# SIM5320_3G_Breakout.net
KiCad netlist of a schematic drawn in EAGLE
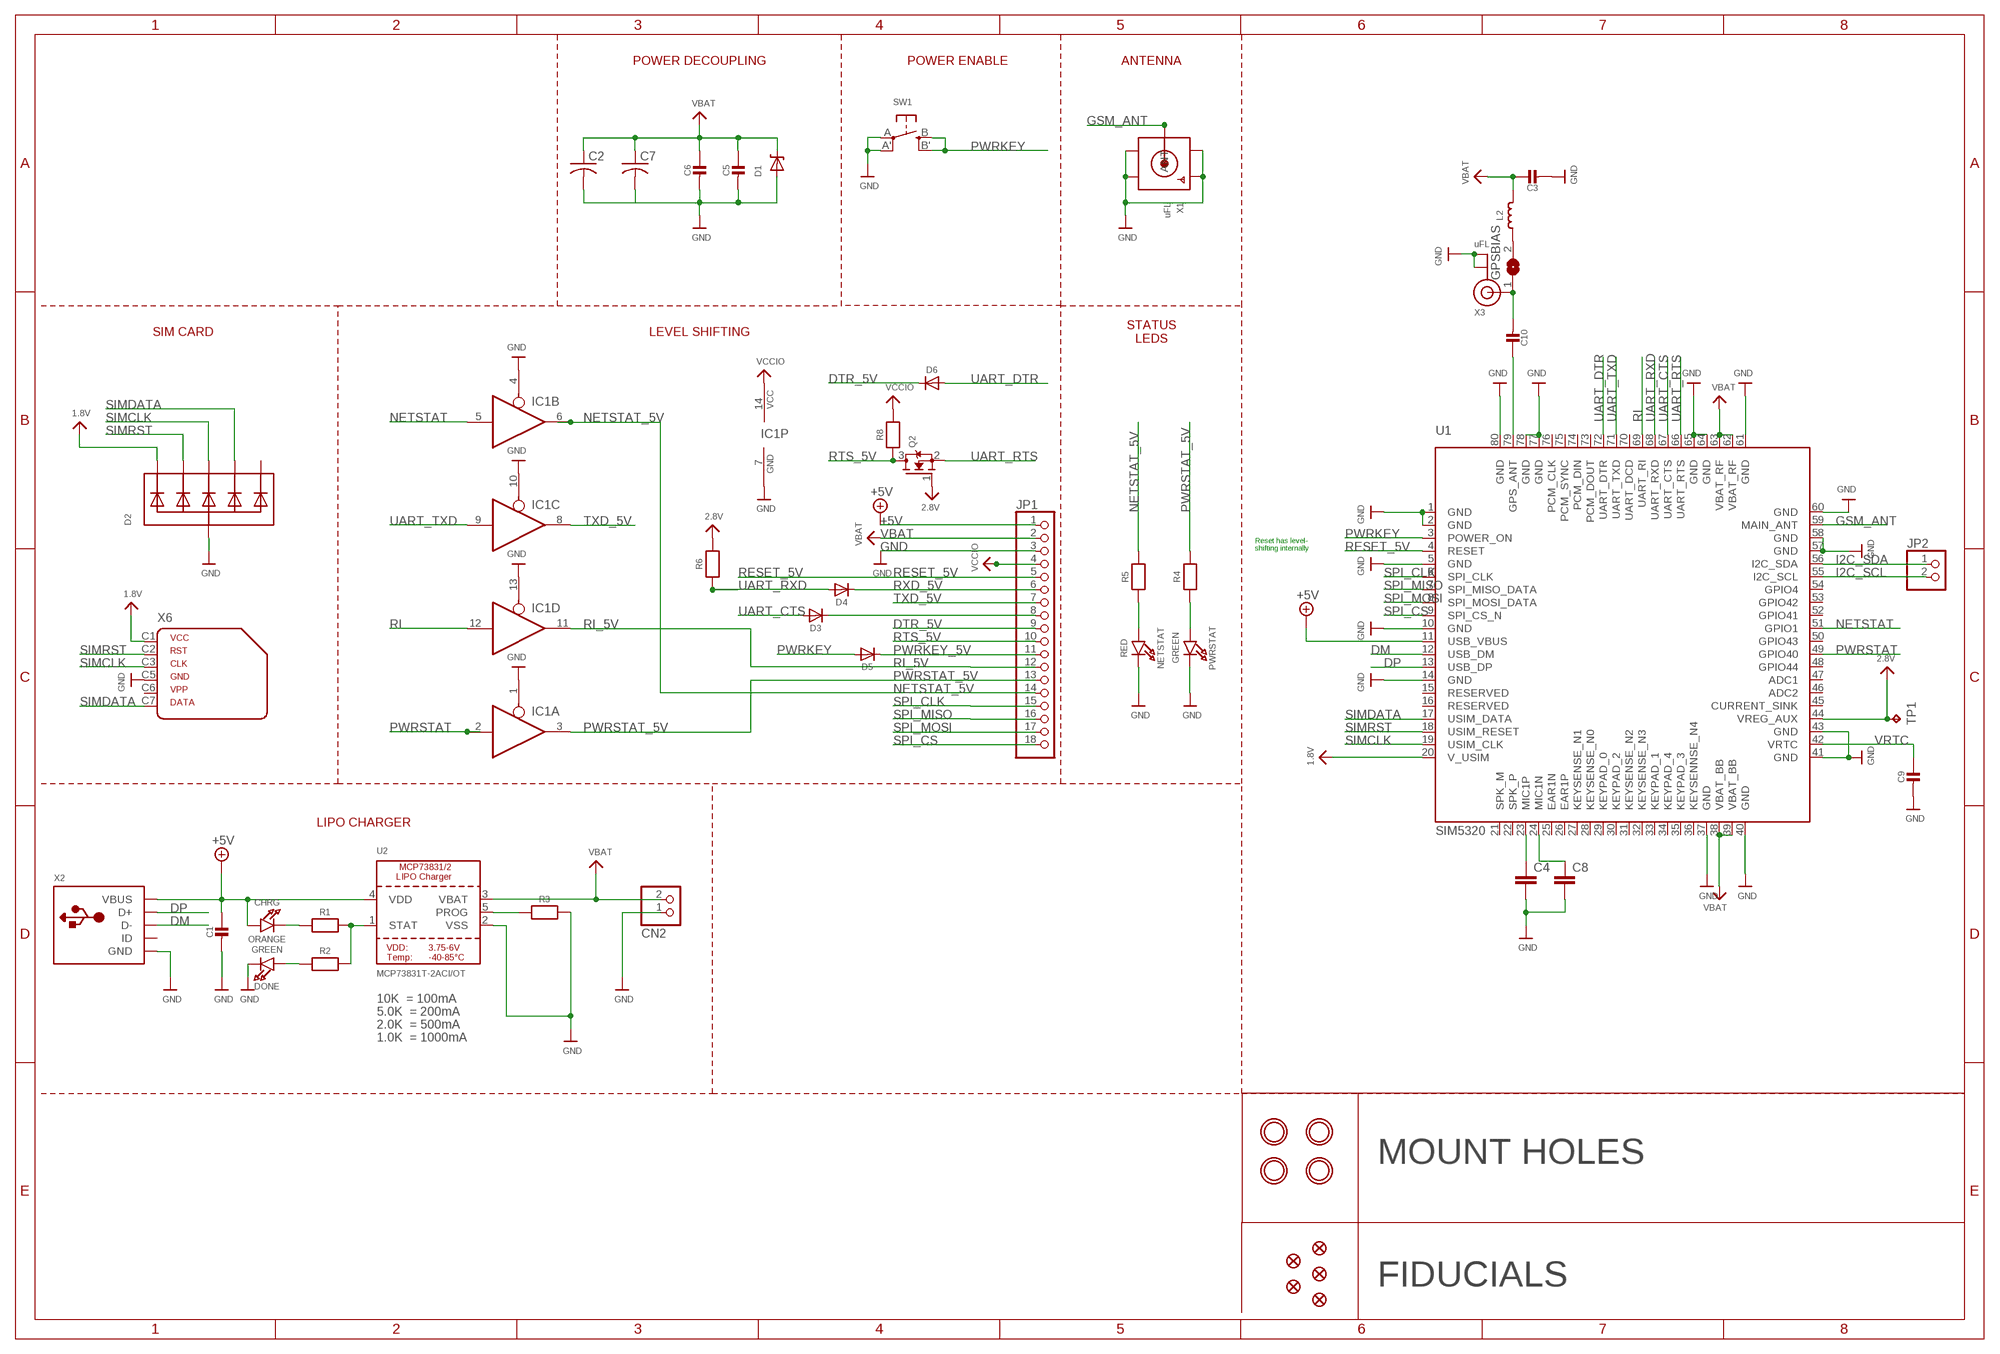
[diagram p0: schematic, sheet 1]

(export (version "E")
  (design (tool "Eeschema 10.0.6"))
  (components
    (comp (ref "C1")
      (value "CAP_CERAMIC0805-NOOUTLINE")
      (footprint "eagle-import:0805-NO")
      (libsource (lib "eagle-import") (part "CAP_CERAMIC0805-NOOUTLINE"))
    )
    (comp (ref "C2")
      (value "C-USC1210")
      (footprint "eagle-import:C1210")
      (libsource (lib "eagle-import") (part "C-USC1210"))
    )
    (comp (ref "C3")
      (value "CAP_CERAMIC0805-NOOUTLINE")
      (footprint "eagle-import:0805-NO")
      (libsource (lib "eagle-import") (part "CAP_CERAMIC0805-NOOUTLINE"))
    )
    (comp (ref "C4")
      (value "C-EUC1210")
      (footprint "eagle-import:C1210")
      (libsource (lib "eagle-import") (part "C-EUC1210"))
    )
    (comp (ref "C5")
      (value "CAP_CERAMIC0805-NOOUTLINE")
      (footprint "eagle-import:0805-NO")
      (libsource (lib "eagle-import") (part "CAP_CERAMIC0805-NOOUTLINE"))
    )
    (comp (ref "C6")
      (value "CAP_CERAMIC0805-NOOUTLINE")
      (footprint "eagle-import:0805-NO")
      (libsource (lib "eagle-import") (part "CAP_CERAMIC0805-NOOUTLINE"))
    )
    (comp (ref "C7")
      (value "C-USC1210")
      (footprint "eagle-import:C1210")
      (libsource (lib "eagle-import") (part "C-USC1210"))
    )
    (comp (ref "C8")
      (value "C-EUC1210")
      (footprint "eagle-import:C1210")
      (libsource (lib "eagle-import") (part "C-EUC1210"))
    )
    (comp (ref "C9")
      (value "CAP_CERAMIC0805-NOOUTLINE")
      (footprint "eagle-import:0805-NO")
      (libsource (lib "eagle-import") (part "CAP_CERAMIC0805-NOOUTLINE"))
    )
    (comp (ref "C10")
      (value "CAP_CERAMIC0805-NOOUTLINE")
      (footprint "eagle-import:0805-NO")
      (libsource (lib "eagle-import") (part "CAP_CERAMIC0805-NOOUTLINE"))
    )
    (comp (ref "CHRG")
      (value "ORANGE")
      (footprint "eagle-import:CHIPLED_0805_NOOUTLINE")
      (libsource (lib "eagle-import") (part "LED0805_NOOUTLINE"))
    )
    (comp (ref "CN2")
      (value "JST_2PIN")
      (footprint "eagle-import:JSTPH2")
      (libsource (lib "eagle-import") (part "JST_2PIN"))
    )
    (comp (ref "D1")
      (value "DIODE-ZENERSOD123")
      (footprint "eagle-import:SOD-123")
      (libsource (lib "eagle-import") (part "DIODE-ZENERSOD123"))
    )
    (comp (ref "D2")
      (value "TVSARRAY_5LANE")
      (footprint "eagle-import:SOT363")
      (libsource (lib "eagle-import") (part "TVSARRAY_5LANE"))
    )
    (comp (ref "D3")
      (value "DIODESOD-323")
      (footprint "eagle-import:SOD-323")
      (libsource (lib "eagle-import") (part "DIODESOD-323"))
    )
    (comp (ref "D4")
      (value "DIODESOD-323")
      (footprint "eagle-import:SOD-323")
      (libsource (lib "eagle-import") (part "DIODESOD-323"))
    )
    (comp (ref "D5")
      (value "DIODESOD-323")
      (footprint "eagle-import:SOD-323")
      (libsource (lib "eagle-import") (part "DIODESOD-323"))
    )
    (comp (ref "D6")
      (value "DIODESOD-323")
      (footprint "eagle-import:SOD-323")
      (libsource (lib "eagle-import") (part "DIODESOD-323"))
    )
    (comp (ref "DONE")
      (value "GREEN")
      (footprint "eagle-import:CHIPLED_0805_NOOUTLINE")
      (libsource (lib "eagle-import") (part "LED0805_NOOUTLINE"))
    )
    (comp (ref "FID1")
      (value "FIDUCIAL\"\"")
      (footprint "eagle-import:FIDUCIAL_1MM")
      (libsource (lib "eagle-import") (part "FIDUCIAL{dblquote}{dblquote}"))
    )
    (comp (ref "FID2")
      (value "FIDUCIAL\"\"")
      (footprint "eagle-import:FIDUCIAL_1MM")
      (libsource (lib "eagle-import") (part "FIDUCIAL{dblquote}{dblquote}"))
    )
    (comp (ref "FID3")
      (value "FIDUCIAL\"\"")
      (footprint "eagle-import:FIDUCIAL_1MM")
      (libsource (lib "eagle-import") (part "FIDUCIAL{dblquote}{dblquote}"))
    )
    (comp (ref "FID4")
      (value "FIDUCIAL\"\"")
      (footprint "eagle-import:FIDUCIAL_1MM")
      (libsource (lib "eagle-import") (part "FIDUCIAL{dblquote}{dblquote}"))
    )
    (comp (ref "FID5")
      (value "FIDUCIAL\"\"")
      (footprint "eagle-import:FIDUCIAL_1MM")
      (libsource (lib "eagle-import") (part "FIDUCIAL{dblquote}{dblquote}"))
    )
    (comp (ref "GPSBIAS")
      (value "SOLDERJUMPER")
      (footprint "eagle-import:SOLDERJUMPER_ARROW_NOPASTE")
      (libsource (lib "eagle-import") (part "SOLDERJUMPER"))
    )
    (comp (ref "IC1")
      (value "74ABT125PW")
      (footprint "eagle-import:TSSOP14")
      (libsource (lib "eagle-import") (part "74125PWABT"))
    )
    (comp (ref "JP1")
      (value "HEADER-1X18")
      (footprint "eagle-import:1X18_ROUND70")
      (libsource (lib "eagle-import") (part "HEADER-1X18"))
    )
    (comp (ref "JP2")
      (value "HEADER-1X2ROUND")
      (footprint "eagle-import:1X02_ROUND")
      (libsource (lib "eagle-import") (part "HEADER-1X2ROUND"))
    )
    (comp (ref "L2")
      (value "INDUCTOR_0805MP")
      (footprint "eagle-import:_0805MP")
      (libsource (lib "eagle-import") (part "INDUCTOR_0805MP"))
    )
    (comp (ref "NETSTAT")
      (value "RED")
      (footprint "eagle-import:CHIPLED_0805_NOOUTLINE")
      (libsource (lib "eagle-import") (part "LED0805_NOOUTLINE"))
    )
    (comp (ref "PWRSTAT")
      (value "GREEN")
      (footprint "eagle-import:CHIPLED_0805_NOOUTLINE")
      (libsource (lib "eagle-import") (part "LED0805_NOOUTLINE"))
    )
    (comp (ref "Q2")
      (value "MOSFET-NWIDE")
      (footprint "eagle-import:SOT23-WIDE")
      (libsource (lib "eagle-import") (part "MOSFET-NWIDE"))
    )
    (comp (ref "R1")
      (value "RESISTOR0805_NOOUTLINE")
      (footprint "eagle-import:0805-NO")
      (libsource (lib "eagle-import") (part "RESISTOR0805_NOOUTLINE"))
    )
    (comp (ref "R2")
      (value "RESISTOR0805_NOOUTLINE")
      (footprint "eagle-import:0805-NO")
      (libsource (lib "eagle-import") (part "RESISTOR0805_NOOUTLINE"))
    )
    (comp (ref "R3")
      (value "RESISTOR0805_NOOUTLINE")
      (footprint "eagle-import:0805-NO")
      (libsource (lib "eagle-import") (part "RESISTOR0805_NOOUTLINE"))
    )
    (comp (ref "R4")
      (value "RESISTOR0805_NOOUTLINE")
      (footprint "eagle-import:0805-NO")
      (libsource (lib "eagle-import") (part "RESISTOR0805_NOOUTLINE"))
    )
    (comp (ref "R5")
      (value "RESISTOR0805_NOOUTLINE")
      (footprint "eagle-import:0805-NO")
      (libsource (lib "eagle-import") (part "RESISTOR0805_NOOUTLINE"))
    )
    (comp (ref "R6")
      (value "RESISTOR0805_NOOUTLINE")
      (footprint "eagle-import:0805-NO")
      (libsource (lib "eagle-import") (part "RESISTOR0805_NOOUTLINE"))
    )
    (comp (ref "R8")
      (value "RESISTOR0805_NOOUTLINE")
      (footprint "eagle-import:0805-NO")
      (libsource (lib "eagle-import") (part "RESISTOR0805_NOOUTLINE"))
    )
    (comp (ref "SW1")
      (value "SWITCH_TACT_SMT4.6X2.8")
      (footprint "eagle-import:BTN_KMR2_4.6X2.8")
      (libsource (lib "eagle-import") (part "SWITCH_TACT_SMT4.6X2.8"))
    )
    (comp (ref "TP1")
      (value "TPTP11R")
      (footprint "eagle-import:TP11R")
      (libsource (lib "eagle-import") (part "TPTP11R"))
    )
    (comp (ref "U$32")
      (value "MOUNTINGHOLE2.5")
      (footprint "eagle-import:MOUNTINGHOLE_2.5_PLATED")
      (libsource (lib "eagle-import") (part "MOUNTINGHOLE2.5"))
    )
    (comp (ref "U$33")
      (value "MOUNTINGHOLE2.5")
      (footprint "eagle-import:MOUNTINGHOLE_2.5_PLATED")
      (libsource (lib "eagle-import") (part "MOUNTINGHOLE2.5"))
    )
    (comp (ref "U$34")
      (value "MOUNTINGHOLE2.5")
      (footprint "eagle-import:MOUNTINGHOLE_2.5_PLATED")
      (libsource (lib "eagle-import") (part "MOUNTINGHOLE2.5"))
    )
    (comp (ref "U$43")
      (value "MOUNTINGHOLE2.5")
      (footprint "eagle-import:MOUNTINGHOLE_2.5_PLATED")
      (libsource (lib "eagle-import") (part "MOUNTINGHOLE2.5"))
    )
    (comp (ref "U1")
      (value "SIM5320")
      (footprint "eagle-import:SIM5320")
      (libsource (lib "eagle-import") (part "GSM_SIM5320_LITERAL"))
    )
    (comp (ref "U2")
      (value "MCP73831T-2ACI/OT")
      (footprint "eagle-import:SOT23-5")
      (libsource (lib "eagle-import") (part "MCP73831/2"))
    )
    (comp (ref "X1")
      (value "uFL")
      (footprint "eagle-import:SMA_EDGELAUNCH_UFL")
      (libsource (lib "eagle-import") (part "SMACONNECTOR_EDGE_UFL"))
    )
    (comp (ref "X2")
      (value "USBMICRO_20329")
      (footprint "eagle-import:4UCONN_20329")
      (libsource (lib "eagle-import") (part "USBMICRO_20329"))
    )
    (comp (ref "X3")
      (value "uFL")
      (footprint "eagle-import:U.FL")
      (libsource (lib "eagle-import") (part "ANTENNA_U.FL"))
    )
    (comp (ref "X6")
      (value "SIM_LOCKAMPHENOL")
      (footprint "eagle-import:C707_10M006_512_2")
      (libsource (lib "eagle-import") (part "SIM_LOCKAMPHENOL"))
    )
  )
  (nets
    (net (code "1") (name "+5V") (class "Default")
      (node (ref "C1") (pin "1") (pinfunction "1_1") (pintype "passive"))
      (node (ref "CHRG") (pin "A") (pinfunction "A_A") (pintype "passive"))
      (node (ref "JP1") (pin "1") (pinfunction "1_1") (pintype "passive"))
      (node (ref "U1") (pin "11") (pinfunction "USB_VBUS_11") (pintype "bidirectional"))
      (node (ref "U2") (pin "4") (pinfunction "VDD_4") (pintype "power_in"))
      (node (ref "X2") (pin "VBUS") (pinfunction "VBUS_VBUS") (pintype "power_in"))
    )
    (net (code "2") (name "/DM") (class "Default")
      (node (ref "U1") (pin "12") (pinfunction "USB_DM_12") (pintype "bidirectional"))
      (node (ref "X2") (pin "D-") (pinfunction "D-_D-") (pintype "bidirectional"))
    )
    (net (code "3") (name "/DP") (class "Default")
      (node (ref "U1") (pin "13") (pinfunction "USB_DP_13") (pintype "bidirectional"))
      (node (ref "X2") (pin "D+") (pinfunction "D+_D+") (pintype "bidirectional"))
    )
    (net (code "4") (name "/DTR_5V") (class "Default")
      (node (ref "D6") (pin "C") (pinfunction "C_C") (pintype "passive"))
      (node (ref "JP1") (pin "9") (pinfunction "9_9") (pintype "passive"))
    )
    (net (code "5") (name "/GSM_ANT") (class "Default")
      (node (ref "U1") (pin "59") (pinfunction "MAIN_ANT_59") (pintype "bidirectional"))
      (node (ref "X1") (pin "P") (pinfunction "ANT_P") (pintype "bidirectional"))
    )
    (net (code "6") (name "/I2C_SCL") (class "Default")
      (node (ref "JP2") (pin "2") (pinfunction "2_2") (pintype "passive"))
      (node (ref "U1") (pin "55") (pinfunction "I2C_SCL_55") (pintype "bidirectional"))
    )
    (net (code "7") (name "/I2C_SDA") (class "Default")
      (node (ref "JP2") (pin "1") (pinfunction "1_1") (pintype "passive"))
      (node (ref "U1") (pin "56") (pinfunction "I2C_SDA_56") (pintype "bidirectional"))
    )
    (net (code "8") (name "/NETSTAT") (class "Default")
      (node (ref "IC1") (pin "5") (pinfunction "I_5") (pintype "input"))
      (node (ref "U1") (pin "51") (pinfunction "GPIO1_51") (pintype "bidirectional"))
    )
    (net (code "9") (name "/NETSTAT_5V") (class "Default")
      (node (ref "IC1") (pin "6") (pinfunction "O_6") (pintype "tri_state"))
      (node (ref "JP1") (pin "14") (pinfunction "14_14") (pintype "passive"))
      (node (ref "R5") (pin "2") (pinfunction "2_2") (pintype "passive"))
    )
    (net (code "10") (name "/PWRKEY") (class "Default")
      (node (ref "D5") (pin "A") (pinfunction "A_A") (pintype "passive"))
      (node (ref "SW1") (pin "B") (pinfunction "S_B") (pintype "passive"))
      (node (ref "SW1") (pin "B'") (pinfunction "S1_B'") (pintype "passive"))
      (node (ref "U1") (pin "3") (pinfunction "POWER_ON_3") (pintype "bidirectional"))
    )
    (net (code "11") (name "/PWRKEY_5V") (class "Default")
      (node (ref "D5") (pin "C") (pinfunction "C_C") (pintype "passive"))
      (node (ref "JP1") (pin "11") (pinfunction "11_11") (pintype "passive"))
    )
    (net (code "12") (name "/PWRSTAT") (class "Default")
      (node (ref "IC1") (pin "2") (pinfunction "I_2") (pintype "input"))
      (node (ref "U1") (pin "49") (pinfunction "GPIO40_49") (pintype "bidirectional"))
    )
    (net (code "13") (name "/PWRSTAT_5V") (class "Default")
      (node (ref "IC1") (pin "3") (pinfunction "O_3") (pintype "tri_state"))
      (node (ref "JP1") (pin "13") (pinfunction "13_13") (pintype "passive"))
      (node (ref "R4") (pin "2") (pinfunction "2_2") (pintype "passive"))
    )
    (net (code "14") (name "/RESET_5V") (class "Default")
      (node (ref "JP1") (pin "5") (pinfunction "5_5") (pintype "passive"))
      (node (ref "U1") (pin "4") (pinfunction "RESET_4") (pintype "bidirectional"))
    )
    (net (code "15") (name "/RI") (class "Default")
      (node (ref "IC1") (pin "12") (pinfunction "I_12") (pintype "input"))
      (node (ref "U1") (pin "69") (pinfunction "UART_RI_69") (pintype "bidirectional"))
    )
    (net (code "16") (name "/RI_5V") (class "Default")
      (node (ref "IC1") (pin "11") (pinfunction "O_11") (pintype "tri_state"))
      (node (ref "JP1") (pin "12") (pinfunction "12_12") (pintype "passive"))
    )
    (net (code "17") (name "/RTS_5V") (class "Default")
      (node (ref "JP1") (pin "10") (pinfunction "10_10") (pintype "passive"))
      (node (ref "Q2") (pin "3") (pinfunction "D_3") (pintype "bidirectional"))
      (node (ref "R8") (pin "1") (pinfunction "1_1") (pintype "passive"))
    )
    (net (code "18") (name "/RXD_5V") (class "Default")
      (node (ref "D4") (pin "C") (pinfunction "C_C") (pintype "passive"))
      (node (ref "JP1") (pin "6") (pinfunction "6_6") (pintype "passive"))
    )
    (net (code "19") (name "/SIMCLK") (class "Default")
      (node (ref "D2") (pin "4") (pinfunction "C3_4") (pintype "passive"))
      (node (ref "U1") (pin "19") (pinfunction "USIM_CLK_19") (pintype "bidirectional"))
      (node (ref "X6") (pin "C3") (pinfunction "3_C3") (pintype "passive"))
    )
    (net (code "20") (name "/SIMDATA") (class "Default")
      (node (ref "D2") (pin "5") (pinfunction "C4_5") (pintype "passive"))
      (node (ref "U1") (pin "17") (pinfunction "USIM_DATA_17") (pintype "bidirectional"))
      (node (ref "X6") (pin "C7") (pinfunction "6_C7") (pintype "passive"))
    )
    (net (code "21") (name "/SIMRST") (class "Default")
      (node (ref "D2") (pin "3") (pinfunction "C2_3") (pintype "passive"))
      (node (ref "U1") (pin "18") (pinfunction "USIM_RESET_18") (pintype "bidirectional"))
      (node (ref "X6") (pin "C2") (pinfunction "2_C2") (pintype "passive"))
    )
    (net (code "22") (name "/SPI_CLK") (class "Default")
      (node (ref "JP1") (pin "15") (pinfunction "15_15") (pintype "passive"))
      (node (ref "U1") (pin "6") (pinfunction "SPI_CLK_6") (pintype "bidirectional"))
    )
    (net (code "23") (name "/SPI_CS") (class "Default")
      (node (ref "JP1") (pin "18") (pinfunction "18_18") (pintype "passive"))
      (node (ref "U1") (pin "9") (pinfunction "SPI_CS_N_9") (pintype "bidirectional"))
    )
    (net (code "24") (name "/SPI_MISO") (class "Default")
      (node (ref "JP1") (pin "16") (pinfunction "16_16") (pintype "passive"))
      (node (ref "U1") (pin "7") (pinfunction "SPI_MISO_DATA_7") (pintype "bidirectional"))
    )
    (net (code "25") (name "/SPI_MOSI") (class "Default")
      (node (ref "JP1") (pin "17") (pinfunction "17_17") (pintype "passive"))
      (node (ref "U1") (pin "8") (pinfunction "SPI_MOSI_DATA_8") (pintype "bidirectional"))
    )
    (net (code "26") (name "/TXD_5V") (class "Default")
      (node (ref "IC1") (pin "8") (pinfunction "O_8") (pintype "tri_state"))
      (node (ref "JP1") (pin "7") (pinfunction "7_7") (pintype "passive"))
    )
    (net (code "27") (name "/UART_CTS") (class "Default")
      (node (ref "D3") (pin "A") (pinfunction "A_A") (pintype "passive"))
      (node (ref "U1") (pin "67") (pinfunction "UART_CTS_67") (pintype "bidirectional"))
    )
    (net (code "28") (name "/UART_DTR") (class "Default")
      (node (ref "D6") (pin "A") (pinfunction "A_A") (pintype "passive"))
      (node (ref "U1") (pin "72") (pinfunction "UART_DTR_72") (pintype "bidirectional"))
    )
    (net (code "29") (name "/UART_RTS") (class "Default")
      (node (ref "Q2") (pin "2") (pinfunction "S_2") (pintype "bidirectional"))
      (node (ref "U1") (pin "66") (pinfunction "UART_RTS_66") (pintype "bidirectional"))
    )
    (net (code "30") (name "/UART_RXD") (class "Default")
      (node (ref "D4") (pin "A") (pinfunction "A_A") (pintype "passive"))
      (node (ref "R6") (pin "1") (pinfunction "1_1") (pintype "passive"))
      (node (ref "U1") (pin "68") (pinfunction "UART_RXD_68") (pintype "bidirectional"))
    )
    (net (code "31") (name "/UART_TXD") (class "Default")
      (node (ref "IC1") (pin "9") (pinfunction "I_9") (pintype "input"))
      (node (ref "U1") (pin "71") (pinfunction "UART_TXD_71") (pintype "bidirectional"))
    )
    (net (code "32") (name "/VRTC") (class "Default")
      (node (ref "C9") (pin "1") (pinfunction "1_1") (pintype "passive"))
      (node (ref "U1") (pin "42") (pinfunction "VRTC_42") (pintype "bidirectional"))
    )
    (net (code "33") (name "1.8V") (class "Default")
      (node (ref "D2") (pin "1") (pinfunction "C1_1") (pintype "passive"))
      (node (ref "U1") (pin "20") (pinfunction "V_USIM_20") (pintype "bidirectional"))
      (node (ref "X6") (pin "C1") (pinfunction "1_C1") (pintype "passive"))
    )
    (net (code "34") (name "2.8V") (class "Default")
      (node (ref "Q2") (pin "1") (pinfunction "G_1") (pintype "bidirectional"))
      (node (ref "R6") (pin "2") (pinfunction "2_2") (pintype "passive"))
      (node (ref "TP1") (pin "TP") (pinfunction "TP_TP") (pintype "input"))
      (node (ref "U1") (pin "44") (pinfunction "VREG_AUX_44") (pintype "bidirectional"))
    )
    (net (code "35") (name "GND") (class "Default")
      (node (ref "C1") (pin "2") (pinfunction "2_2") (pintype "passive"))
      (node (ref "C2") (pin "2") (pinfunction "2_2") (pintype "passive"))
      (node (ref "C3") (pin "2") (pinfunction "2_2") (pintype "passive"))
      (node (ref "C4") (pin "2") (pinfunction "2_2") (pintype "passive"))
      (node (ref "C5") (pin "2") (pinfunction "2_2") (pintype "passive"))
      (node (ref "C6") (pin "2") (pinfunction "2_2") (pintype "passive"))
      (node (ref "C7") (pin "2") (pinfunction "2_2") (pintype "passive"))
      (node (ref "C8") (pin "2") (pinfunction "2_2") (pintype "passive"))
      (node (ref "C9") (pin "2") (pinfunction "2_2") (pintype "passive"))
      (node (ref "CN2") (pin "1") (pinfunction "1_1") (pintype "passive"))
      (node (ref "D1") (pin "A") (pinfunction "A_A") (pintype "passive"))
      (node (ref "D2") (pin "2") (pinfunction "A_2") (pintype "passive"))
      (node (ref "DONE") (pin "C") (pinfunction "C_C") (pintype "passive"))
      (node (ref "IC1") (pin "1") (pinfunction "OE_1") (pintype "input"))
      (node (ref "IC1") (pin "10") (pinfunction "OE_10") (pintype "input"))
      (node (ref "IC1") (pin "13") (pinfunction "OE_13") (pintype "input"))
      (node (ref "IC1") (pin "4") (pinfunction "OE_4") (pintype "input"))
      (node (ref "IC1") (pin "7") (pinfunction "GND_7") (pintype "power_in"))
      (node (ref "JP1") (pin "3") (pinfunction "3_3") (pintype "passive"))
      (node (ref "NETSTAT") (pin "C") (pinfunction "C_C") (pintype "passive"))
      (node (ref "PWRSTAT") (pin "C") (pinfunction "C_C") (pintype "passive"))
      (node (ref "R3") (pin "2") (pinfunction "2_2") (pintype "passive"))
      (node (ref "SW1") (pin "A") (pinfunction "P_A") (pintype "passive"))
      (node (ref "SW1") (pin "A'") (pinfunction "P1_A'") (pintype "passive"))
      (node (ref "U1") (pin "1") (pinfunction "GND_1") (pintype "bidirectional"))
      (node (ref "U1") (pin "10") (pinfunction "GND_10") (pintype "bidirectional"))
      (node (ref "U1") (pin "14") (pinfunction "GND_14") (pintype "bidirectional"))
      (node (ref "U1") (pin "2") (pinfunction "GND_2") (pintype "bidirectional"))
      (node (ref "U1") (pin "37") (pinfunction "GND_37") (pintype "bidirectional"))
      (node (ref "U1") (pin "40") (pinfunction "GND_40") (pintype "bidirectional"))
      (node (ref "U1") (pin "41") (pinfunction "GND_41") (pintype "bidirectional"))
      (node (ref "U1") (pin "43") (pinfunction "GND_43") (pintype "bidirectional"))
      (node (ref "U1") (pin "5") (pinfunction "GND_5") (pintype "bidirectional"))
      (node (ref "U1") (pin "57") (pinfunction "GND_57") (pintype "bidirectional"))
      (node (ref "U1") (pin "58") (pinfunction "GND_58") (pintype "bidirectional"))
      (node (ref "U1") (pin "60") (pinfunction "GND_60") (pintype "bidirectional"))
      (node (ref "U1") (pin "61") (pinfunction "GND_61") (pintype "bidirectional"))
      (node (ref "U1") (pin "64") (pinfunction "GND_64") (pintype "bidirectional"))
      (node (ref "U1") (pin "65") (pinfunction "GND_65") (pintype "bidirectional"))
      (node (ref "U1") (pin "77") (pinfunction "GND_77") (pintype "bidirectional"))
      (node (ref "U1") (pin "78") (pinfunction "GND_78") (pintype "bidirectional"))
      (node (ref "U1") (pin "80") (pinfunction "GND_80") (pintype "bidirectional"))
      (node (ref "U2") (pin "2") (pinfunction "VSS_2") (pintype "power_in"))
      (node (ref "X1") (pin "GND@1") (pinfunction "GND1_GND@1") (pintype "power_in"))
      (node (ref "X1") (pin "GND@2") (pinfunction "GND2_GND@2") (pintype "power_in"))
      (node (ref "X1") (pin "GND@3") (pinfunction "GND3_GND@3") (pintype "power_in"))
      (node (ref "X1") (pin "GND@4") (pinfunction "GND4_GND@4") (pintype "power_in"))
      (node (ref "X2") (pin "BASE@1") (pinfunction "GND_BASE@1") (pintype "power_in"))
      (node (ref "X2") (pin "BASE@2") (pinfunction "GND_BASE@2") (pintype "power_in"))
      (node (ref "X2") (pin "GND") (pinfunction "GND_GND") (pintype "power_in"))
      (node (ref "X2") (pin "SPRT@1") (pinfunction "GND_SPRT@1") (pintype "power_in"))
      (node (ref "X2") (pin "SPRT@2") (pinfunction "GND_SPRT@2") (pintype "power_in"))
      (node (ref "X2") (pin "SPRT@3") (pinfunction "GND_SPRT@3") (pintype "power_in"))
      (node (ref "X2") (pin "SPRT@4") (pinfunction "GND_SPRT@4") (pintype "power_in"))
      (node (ref "X3") (pin "1") (pinfunction "GND_1") (pintype "passive"))
      (node (ref "X3") (pin "2") (pinfunction "GND_2") (pintype "passive"))
      (node (ref "X6") (pin "C5") (pinfunction "4_C5") (pintype "passive"))
    )
    (net (code "36") (name "Net-(CHRG-PadC)") (class "Default")
      (node (ref "CHRG") (pin "C") (pinfunction "C_C") (pintype "passive"))
      (node (ref "R1") (pin "1") (pinfunction "1_1") (pintype "passive"))
    )
    (net (code "37") (name "Net-(D3-PadC)") (class "Default")
      (node (ref "D3") (pin "C") (pinfunction "C_C") (pintype "passive"))
      (node (ref "JP1") (pin "8") (pinfunction "8_8") (pintype "passive"))
    )
    (net (code "38") (name "Net-(DONE-PadA)") (class "Default")
      (node (ref "DONE") (pin "A") (pinfunction "A_A") (pintype "passive"))
      (node (ref "R2") (pin "1") (pinfunction "1_1") (pintype "passive"))
    )
    (net (code "39") (name "Net-(GPSBIAS-Pad2)") (class "Default")
      (node (ref "GPSBIAS") (pin "2") (pinfunction "2_2") (pintype "passive"))
      (node (ref "L2") (pin "1") (pinfunction "1_1") (pintype "passive"))
    )
    (net (code "40") (name "Net-(NETSTAT-PadA)") (class "Default")
      (node (ref "NETSTAT") (pin "A") (pinfunction "A_A") (pintype "passive"))
      (node (ref "R5") (pin "1") (pinfunction "1_1") (pintype "passive"))
    )
    (net (code "41") (name "Net-(PWRSTAT-PadA)") (class "Default")
      (node (ref "PWRSTAT") (pin "A") (pinfunction "A_A") (pintype "passive"))
      (node (ref "R4") (pin "1") (pinfunction "1_1") (pintype "passive"))
    )
    (net (code "42") (name "Net-(U1-GPS_ANT)") (class "Default")
      (node (ref "C10") (pin "1") (pinfunction "1_1") (pintype "passive"))
      (node (ref "U1") (pin "79") (pinfunction "GPS_ANT_79") (pintype "bidirectional"))
    )
    (net (code "43") (name "Net-(U1-MIC1N)") (class "Default")
      (node (ref "C8") (pin "1") (pinfunction "1_1") (pintype "passive"))
      (node (ref "U1") (pin "24") (pinfunction "MIC1N_24") (pintype "bidirectional"))
    )
    (net (code "44") (name "Net-(U1-MIC1P)") (class "Default")
      (node (ref "C4") (pin "1") (pinfunction "1_1") (pintype "passive"))
      (node (ref "U1") (pin "23") (pinfunction "MIC1P_23") (pintype "bidirectional"))
    )
    (net (code "45") (name "Net-(U2-PROG)") (class "Default")
      (node (ref "R3") (pin "1") (pinfunction "1_1") (pintype "passive"))
      (node (ref "U2") (pin "5") (pinfunction "PROG_5") (pintype "input"))
    )
    (net (code "46") (name "Net-(U2-STAT)") (class "Default")
      (node (ref "R1") (pin "2") (pinfunction "2_2") (pintype "passive"))
      (node (ref "R2") (pin "2") (pinfunction "2_2") (pintype "passive"))
      (node (ref "U2") (pin "1") (pinfunction "STAT_1") (pintype "output"))
    )
    (net (code "47") (name "Net-(X3-SIGNAL)") (class "Default")
      (node (ref "C10") (pin "2") (pinfunction "2_2") (pintype "passive"))
      (node (ref "GPSBIAS") (pin "1") (pinfunction "1_1") (pintype "passive"))
      (node (ref "X3") (pin "3") (pinfunction "SIGNAL_3") (pintype "passive"))
    )
    (net (code "48") (name "VBAT") (class "Default")
      (node (ref "C2") (pin "1") (pinfunction "1_1") (pintype "passive"))
      (node (ref "C3") (pin "1") (pinfunction "1_1") (pintype "passive"))
      (node (ref "C5") (pin "1") (pinfunction "1_1") (pintype "passive"))
      (node (ref "C6") (pin "1") (pinfunction "1_1") (pintype "passive"))
      (node (ref "C7") (pin "1") (pinfunction "1_1") (pintype "passive"))
      (node (ref "CN2") (pin "2") (pinfunction "2_2") (pintype "passive"))
      (node (ref "D1") (pin "C") (pinfunction "C_C") (pintype "passive"))
      (node (ref "JP1") (pin "2") (pinfunction "2_2") (pintype "passive"))
      (node (ref "L2") (pin "2") (pinfunction "2_2") (pintype "passive"))
      (node (ref "U1") (pin "38") (pinfunction "VBAT_BB_38") (pintype "bidirectional"))
      (node (ref "U1") (pin "39") (pinfunction "VBAT_BB_39") (pintype "bidirectional"))
      (node (ref "U1") (pin "62") (pinfunction "VBAT_RF_62") (pintype "bidirectional"))
      (node (ref "U1") (pin "63") (pinfunction "VBAT_RF_63") (pintype "bidirectional"))
      (node (ref "U2") (pin "3") (pinfunction "VBAT_3") (pintype "power_in"))
    )
    (net (code "49") (name "VCCIO") (class "Default")
      (node (ref "IC1") (pin "14") (pinfunction "VCC_14") (pintype "power_in"))
      (node (ref "JP1") (pin "4") (pinfunction "4_4") (pintype "passive"))
      (node (ref "R8") (pin "2") (pinfunction "2_2") (pintype "passive"))
    )
    (net (code "50") (name "unconnected-(D2-C5-Pad6)") (class "Default")
      (node (ref "D2") (pin "6") (pinfunction "C5_6") (pintype "passive"))
    )
    (net (code "51") (name "unconnected-(U1-ADC1-Pad47)") (class "Default")
      (node (ref "U1") (pin "47") (pinfunction "ADC1_47") (pintype "bidirectional"))
    )
    (net (code "52") (name "unconnected-(U1-ADC2-Pad46)") (class "Default")
      (node (ref "U1") (pin "46") (pinfunction "ADC2_46") (pintype "bidirectional"))
    )
    (net (code "53") (name "unconnected-(U1-CURRENT_SINK-Pad45)") (class "Default")
      (node (ref "U1") (pin "45") (pinfunction "CURRENT_SINK_45") (pintype "bidirectional"))
    )
    (net (code "54") (name "unconnected-(U1-EAR1N-Pad25)") (class "Default")
      (node (ref "U1") (pin "25") (pinfunction "EAR1N_25") (pintype "bidirectional"))
    )
    (net (code "55") (name "unconnected-(U1-EAR1P-Pad26)") (class "Default")
      (node (ref "U1") (pin "26") (pinfunction "EAR1P_26") (pintype "bidirectional"))
    )
    (net (code "56") (name "unconnected-(U1-GPIO4-Pad54)") (class "Default")
      (node (ref "U1") (pin "54") (pinfunction "GPIO4_54") (pintype "bidirectional"))
    )
    (net (code "57") (name "unconnected-(U1-GPIO41-Pad52)") (class "Default")
      (node (ref "U1") (pin "52") (pinfunction "GPIO41_52") (pintype "bidirectional"))
    )
    (net (code "58") (name "unconnected-(U1-GPIO42-Pad53)") (class "Default")
      (node (ref "U1") (pin "53") (pinfunction "GPIO42_53") (pintype "bidirectional"))
    )
    (net (code "59") (name "unconnected-(U1-GPIO43-Pad50)") (class "Default")
      (node (ref "U1") (pin "50") (pinfunction "GPIO43_50") (pintype "bidirectional"))
    )
    (net (code "60") (name "unconnected-(U1-GPIO44-Pad48)") (class "Default")
      (node (ref "U1") (pin "48") (pinfunction "GPIO44_48") (pintype "bidirectional"))
    )
    (net (code "61") (name "unconnected-(U1-KEYPAD_0-Pad29)") (class "Default")
      (node (ref "U1") (pin "29") (pinfunction "KEYPAD_0_29") (pintype "bidirectional"))
    )
    (net (code "62") (name "unconnected-(U1-KEYPAD_1-Pad33)") (class "Default")
      (node (ref "U1") (pin "33") (pinfunction "KEYPAD_1_33") (pintype "bidirectional"))
    )
    (net (code "63") (name "unconnected-(U1-KEYPAD_2-Pad30)") (class "Default")
      (node (ref "U1") (pin "30") (pinfunction "KEYPAD_2_30") (pintype "bidirectional"))
    )
    (net (code "64") (name "unconnected-(U1-KEYPAD_3-Pad35)") (class "Default")
      (node (ref "U1") (pin "35") (pinfunction "KEYPAD_3_35") (pintype "bidirectional"))
    )
    (net (code "65") (name "unconnected-(U1-KEYPAD_4-Pad34)") (class "Default")
      (node (ref "U1") (pin "34") (pinfunction "KEYPAD_4_34") (pintype "bidirectional"))
    )
    (net (code "66") (name "unconnected-(U1-KEYSENNSE_N4-Pad36)") (class "Default")
      (node (ref "U1") (pin "36") (pinfunction "KEYSENNSE_N4_36") (pintype "bidirectional"))
    )
    (net (code "67") (name "unconnected-(U1-KEYSENSE_N0-Pad28)") (class "Default")
      (node (ref "U1") (pin "28") (pinfunction "KEYSENSE_N0_28") (pintype "bidirectional"))
    )
    (net (code "68") (name "unconnected-(U1-KEYSENSE_N1-Pad27)") (class "Default")
      (node (ref "U1") (pin "27") (pinfunction "KEYSENSE_N1_27") (pintype "bidirectional"))
    )
    (net (code "69") (name "unconnected-(U1-KEYSENSE_N2-Pad31)") (class "Default")
      (node (ref "U1") (pin "31") (pinfunction "KEYSENSE_N2_31") (pintype "bidirectional"))
    )
    (net (code "70") (name "unconnected-(U1-KEYSENSE_N3-Pad32)") (class "Default")
      (node (ref "U1") (pin "32") (pinfunction "KEYSENSE_N3_32") (pintype "bidirectional"))
    )
    (net (code "71") (name "unconnected-(U1-PCM_CLK-Pad76)") (class "Default")
      (node (ref "U1") (pin "76") (pinfunction "PCM_CLK_76") (pintype "bidirectional"))
    )
    (net (code "72") (name "unconnected-(U1-PCM_DIN-Pad74)") (class "Default")
      (node (ref "U1") (pin "74") (pinfunction "PCM_DIN_74") (pintype "bidirectional"))
    )
    (net (code "73") (name "unconnected-(U1-PCM_DOUT-Pad73)") (class "Default")
      (node (ref "U1") (pin "73") (pinfunction "PCM_DOUT_73") (pintype "bidirectional"))
    )
    (net (code "74") (name "unconnected-(U1-PCM_SYNC-Pad75)") (class "Default")
      (node (ref "U1") (pin "75") (pinfunction "PCM_SYNC_75") (pintype "bidirectional"))
    )
    (net (code "75") (name "unconnected-(U1-RESERVED-Pad15)") (class "Default")
      (node (ref "U1") (pin "15") (pinfunction "RESERVED_15") (pintype "bidirectional"))
    )
    (net (code "76") (name "unconnected-(U1-RESERVED-Pad16)") (class "Default")
      (node (ref "U1") (pin "16") (pinfunction "RESERVED_16") (pintype "bidirectional"))
    )
    (net (code "77") (name "unconnected-(U1-SPK_M-Pad21)") (class "Default")
      (node (ref "U1") (pin "21") (pinfunction "SPK_M_21") (pintype "bidirectional"))
    )
    (net (code "78") (name "unconnected-(U1-SPK_P-Pad22)") (class "Default")
      (node (ref "U1") (pin "22") (pinfunction "SPK_P_22") (pintype "bidirectional"))
    )
    (net (code "79") (name "unconnected-(U1-UART_DCD-Pad70)") (class "Default")
      (node (ref "U1") (pin "70") (pinfunction "UART_DCD_70") (pintype "bidirectional"))
    )
    (net (code "80") (name "unconnected-(X2-PadID)") (class "Default")
      (node (ref "X2") (pin "ID") (pinfunction "ID_ID") (pintype "bidirectional"))
    )
    (net (code "81") (name "unconnected-(X6-5-PadC6)") (class "Default")
      (node (ref "X6") (pin "C6") (pinfunction "5_C6") (pintype "passive"))
    )
  )
)
